# untitled.net
KiCad netlist of a schematic drawn in EAGLE
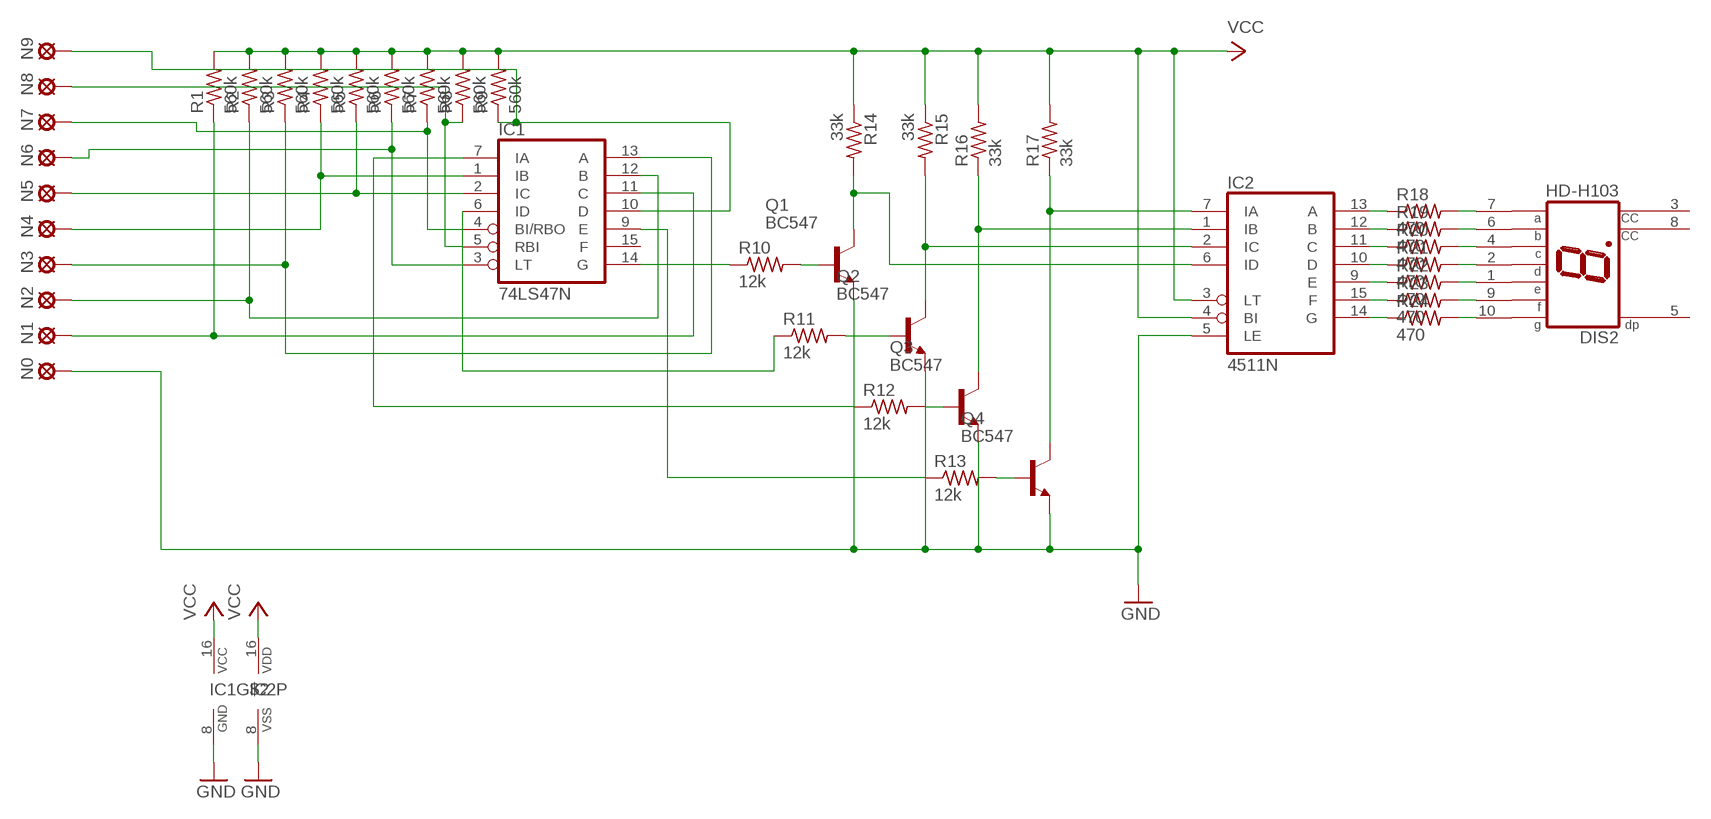
[diagram p0: schematic, sheet 1]

(export (version "E")
  (design (tool "Eeschema 10.0.6"))
  (components
    (comp (ref "DIS2")
      (value "HD-H103")
      (footprint "eagle-import:HDSP-M")
      (libsource (lib "eagle-import") (part "HD-H103"))
    )
    (comp (ref "IC1")
      (value "74LS47N")
      (footprint "eagle-import:DIL16")
      (libsource (lib "eagle-import") (part "7447NLS"))
    )
    (comp (ref "IC2")
      (value "4511N")
      (footprint "eagle-import:DIL16")
      (libsource (lib "eagle-import") (part "4511N"))
    )
    (comp (ref "N0")
      (value "LSP10")
      (footprint "eagle-import:LSP10")
      (libsource (lib "eagle-import") (part "LSP10"))
    )
    (comp (ref "N1")
      (value "LSP10")
      (footprint "eagle-import:LSP10")
      (libsource (lib "eagle-import") (part "LSP10"))
    )
    (comp (ref "N2")
      (value "LSP10")
      (footprint "eagle-import:LSP10")
      (libsource (lib "eagle-import") (part "LSP10"))
    )
    (comp (ref "N3")
      (value "LSP10")
      (footprint "eagle-import:LSP10")
      (libsource (lib "eagle-import") (part "LSP10"))
    )
    (comp (ref "N4")
      (value "LSP10")
      (footprint "eagle-import:LSP10")
      (libsource (lib "eagle-import") (part "LSP10"))
    )
    (comp (ref "N5")
      (value "LSP10")
      (footprint "eagle-import:LSP10")
      (libsource (lib "eagle-import") (part "LSP10"))
    )
    (comp (ref "N6")
      (value "LSP10")
      (footprint "eagle-import:LSP10")
      (libsource (lib "eagle-import") (part "LSP10"))
    )
    (comp (ref "N7")
      (value "LSP10")
      (footprint "eagle-import:LSP10")
      (libsource (lib "eagle-import") (part "LSP10"))
    )
    (comp (ref "N8")
      (value "LSP10")
      (footprint "eagle-import:LSP10")
      (libsource (lib "eagle-import") (part "LSP10"))
    )
    (comp (ref "N9")
      (value "LSP10")
      (footprint "eagle-import:LSP10")
      (libsource (lib "eagle-import") (part "LSP10"))
    )
    (comp (ref "Q1")
      (value "BC547")
      (footprint "eagle-import:TO92")
      (libsource (lib "eagle-import") (part "BC547"))
    )
    (comp (ref "Q2")
      (value "BC547")
      (footprint "eagle-import:TO92")
      (libsource (lib "eagle-import") (part "BC547"))
    )
    (comp (ref "Q3")
      (value "BC547")
      (footprint "eagle-import:TO92")
      (libsource (lib "eagle-import") (part "BC547"))
    )
    (comp (ref "Q4")
      (value "BC547")
      (footprint "eagle-import:TO92")
      (libsource (lib "eagle-import") (part "BC547"))
    )
    (comp (ref "R1")
      (value "560k")
      (footprint "eagle-import:0204_7")
      (libsource (lib "eagle-import") (part "R-US_0204/7"))
    )
    (comp (ref "R2")
      (value "560k")
      (footprint "eagle-import:0204_7")
      (libsource (lib "eagle-import") (part "R-US_0204/7"))
    )
    (comp (ref "R3")
      (value "560k")
      (footprint "eagle-import:0204_7")
      (libsource (lib "eagle-import") (part "R-US_0204/7"))
    )
    (comp (ref "R4")
      (value "560k")
      (footprint "eagle-import:0204_7")
      (libsource (lib "eagle-import") (part "R-US_0204/7"))
    )
    (comp (ref "R5")
      (value "560k")
      (footprint "eagle-import:0204_7")
      (libsource (lib "eagle-import") (part "R-US_0204/7"))
    )
    (comp (ref "R6")
      (value "560k")
      (footprint "eagle-import:0204_7")
      (libsource (lib "eagle-import") (part "R-US_0204/7"))
    )
    (comp (ref "R7")
      (value "560k")
      (footprint "eagle-import:0204_7")
      (libsource (lib "eagle-import") (part "R-US_0204/7"))
    )
    (comp (ref "R8")
      (value "560k")
      (footprint "eagle-import:0204_7")
      (libsource (lib "eagle-import") (part "R-US_0204/7"))
    )
    (comp (ref "R9")
      (value "560k")
      (footprint "eagle-import:0204_7")
      (libsource (lib "eagle-import") (part "R-US_0204/7"))
    )
    (comp (ref "R10")
      (value "12k")
      (footprint "eagle-import:0204_7")
      (libsource (lib "eagle-import") (part "R-US_0204/7"))
    )
    (comp (ref "R11")
      (value "12k")
      (footprint "eagle-import:0204_7")
      (libsource (lib "eagle-import") (part "R-US_0204/7"))
    )
    (comp (ref "R12")
      (value "12k")
      (footprint "eagle-import:0204_7")
      (libsource (lib "eagle-import") (part "R-US_0204/7"))
    )
    (comp (ref "R13")
      (value "12k")
      (footprint "eagle-import:0204_7")
      (libsource (lib "eagle-import") (part "R-US_0204/7"))
    )
    (comp (ref "R14")
      (value "33k")
      (footprint "eagle-import:0204_7")
      (libsource (lib "eagle-import") (part "R-US_0204/7"))
    )
    (comp (ref "R15")
      (value "33k")
      (footprint "eagle-import:0204_7")
      (libsource (lib "eagle-import") (part "R-US_0204/7"))
    )
    (comp (ref "R16")
      (value "33k")
      (footprint "eagle-import:0204_7")
      (libsource (lib "eagle-import") (part "R-US_0204/7"))
    )
    (comp (ref "R17")
      (value "33k")
      (footprint "eagle-import:0204_7")
      (libsource (lib "eagle-import") (part "R-US_0204/7"))
    )
    (comp (ref "R18")
      (value "470")
      (footprint "eagle-import:0204_7")
      (libsource (lib "eagle-import") (part "R-US_0204/7"))
    )
    (comp (ref "R19")
      (value "470")
      (footprint "eagle-import:0204_7")
      (libsource (lib "eagle-import") (part "R-US_0204/7"))
    )
    (comp (ref "R20")
      (value "470")
      (footprint "eagle-import:0204_7")
      (libsource (lib "eagle-import") (part "R-US_0204/7"))
    )
    (comp (ref "R21")
      (value "470")
      (footprint "eagle-import:0204_7")
      (libsource (lib "eagle-import") (part "R-US_0204/7"))
    )
    (comp (ref "R22")
      (value "470")
      (footprint "eagle-import:0204_7")
      (libsource (lib "eagle-import") (part "R-US_0204/7"))
    )
    (comp (ref "R23")
      (value "470")
      (footprint "eagle-import:0204_7")
      (libsource (lib "eagle-import") (part "R-US_0204/7"))
    )
    (comp (ref "R24")
      (value "470")
      (footprint "eagle-import:0204_7")
      (libsource (lib "eagle-import") (part "R-US_0204/7"))
    )
  )
  (nets
    (net (code "1") (name "GND") (class "Default")
      (node (ref "IC1") (pin "8") (pinfunction "GND_8") (pintype "power_in"))
      (node (ref "IC2") (pin "5") (pinfunction "LE_5") (pintype "input"))
      (node (ref "IC2") (pin "8") (pinfunction "VSS_8") (pintype "power_in"))
      (node (ref "N0") (pin "MP") (pinfunction "MP_MP") (pintype "passive"))
      (node (ref "Q1") (pin "1") (pinfunction "E_1") (pintype "passive"))
      (node (ref "Q2") (pin "1") (pinfunction "E_1") (pintype "passive"))
      (node (ref "Q3") (pin "1") (pinfunction "E_1") (pintype "passive"))
      (node (ref "Q4") (pin "1") (pinfunction "E_1") (pintype "passive"))
    )
    (net (code "2") (name "Net-(DIS2-A)") (class "Default")
      (node (ref "DIS2") (pin "7") (pinfunction "A_7") (pintype "passive"))
      (node (ref "R18") (pin "2") (pinfunction "2_2") (pintype "passive"))
    )
    (net (code "3") (name "Net-(DIS2-B)") (class "Default")
      (node (ref "DIS2") (pin "6") (pinfunction "B_6") (pintype "passive"))
      (node (ref "R19") (pin "2") (pinfunction "2_2") (pintype "passive"))
    )
    (net (code "4") (name "Net-(DIS2-C)") (class "Default")
      (node (ref "DIS2") (pin "4") (pinfunction "C_4") (pintype "passive"))
      (node (ref "R20") (pin "2") (pinfunction "2_2") (pintype "passive"))
    )
    (net (code "5") (name "Net-(DIS2-D)") (class "Default")
      (node (ref "DIS2") (pin "2") (pinfunction "D_2") (pintype "passive"))
      (node (ref "R21") (pin "2") (pinfunction "2_2") (pintype "passive"))
    )
    (net (code "6") (name "Net-(DIS2-E)") (class "Default")
      (node (ref "DIS2") (pin "1") (pinfunction "E_1") (pintype "passive"))
      (node (ref "R22") (pin "2") (pinfunction "2_2") (pintype "passive"))
    )
    (net (code "7") (name "Net-(DIS2-F)") (class "Default")
      (node (ref "DIS2") (pin "9") (pinfunction "F_9") (pintype "passive"))
      (node (ref "R23") (pin "2") (pinfunction "2_2") (pintype "passive"))
    )
    (net (code "8") (name "Net-(DIS2-G)") (class "Default")
      (node (ref "DIS2") (pin "10") (pinfunction "G_10") (pintype "passive"))
      (node (ref "R24") (pin "2") (pinfunction "2_2") (pintype "passive"))
    )
    (net (code "9") (name "Net-(IC1A-A)") (class "Default")
      (node (ref "IC1") (pin "13") (pinfunction "A_13") (pintype "output"))
      (node (ref "N3") (pin "MP") (pinfunction "MP_MP") (pintype "passive"))
      (node (ref "R3") (pin "1") (pinfunction "1_1") (pintype "passive"))
    )
    (net (code "10") (name "Net-(IC1A-B)") (class "Default")
      (node (ref "IC1") (pin "12") (pinfunction "B_12") (pintype "output"))
      (node (ref "N2") (pin "MP") (pinfunction "MP_MP") (pintype "passive"))
      (node (ref "R2") (pin "1") (pinfunction "1_1") (pintype "passive"))
    )
    (net (code "11") (name "Net-(IC1A-BI{slash}RBO)") (class "Default")
      (node (ref "IC1") (pin "4") (pinfunction "BI/RBO_4") (pintype "input"))
      (node (ref "N7") (pin "MP") (pinfunction "MP_MP") (pintype "passive"))
      (node (ref "R7") (pin "1") (pinfunction "1_1") (pintype "passive"))
    )
    (net (code "12") (name "Net-(IC1A-C)") (class "Default")
      (node (ref "IC1") (pin "11") (pinfunction "C_11") (pintype "output"))
      (node (ref "N1") (pin "MP") (pinfunction "MP_MP") (pintype "passive"))
      (node (ref "R1") (pin "1") (pinfunction "1_1") (pintype "passive"))
    )
    (net (code "13") (name "Net-(IC1A-D)") (class "Default")
      (node (ref "IC1") (pin "10") (pinfunction "D_10") (pintype "output"))
      (node (ref "N9") (pin "MP") (pinfunction "MP_MP") (pintype "passive"))
      (node (ref "R9") (pin "1") (pinfunction "1_1") (pintype "passive"))
    )
    (net (code "14") (name "Net-(IC1A-E)") (class "Default")
      (node (ref "IC1") (pin "9") (pinfunction "E_9") (pintype "output"))
      (node (ref "R13") (pin "1") (pinfunction "1_1") (pintype "passive"))
    )
    (net (code "15") (name "Net-(IC1A-G)") (class "Default")
      (node (ref "IC1") (pin "14") (pinfunction "G_14") (pintype "output"))
      (node (ref "R10") (pin "1") (pinfunction "1_1") (pintype "passive"))
    )
    (net (code "16") (name "Net-(IC1A-IA)") (class "Default")
      (node (ref "IC1") (pin "7") (pinfunction "IA_7") (pintype "input"))
      (node (ref "R12") (pin "1") (pinfunction "1_1") (pintype "passive"))
    )
    (net (code "17") (name "Net-(IC1A-IB)") (class "Default")
      (node (ref "IC1") (pin "1") (pinfunction "IB_1") (pintype "input"))
      (node (ref "N4") (pin "MP") (pinfunction "MP_MP") (pintype "passive"))
      (node (ref "R4") (pin "1") (pinfunction "1_1") (pintype "passive"))
    )
    (net (code "18") (name "Net-(IC1A-IC)") (class "Default")
      (node (ref "IC1") (pin "2") (pinfunction "IC_2") (pintype "input"))
      (node (ref "N5") (pin "MP") (pinfunction "MP_MP") (pintype "passive"))
      (node (ref "R5") (pin "1") (pinfunction "1_1") (pintype "passive"))
    )
    (net (code "19") (name "Net-(IC1A-ID)") (class "Default")
      (node (ref "IC1") (pin "6") (pinfunction "ID_6") (pintype "input"))
      (node (ref "R11") (pin "1") (pinfunction "1_1") (pintype "passive"))
    )
    (net (code "20") (name "Net-(IC1A-LT)") (class "Default")
      (node (ref "IC1") (pin "3") (pinfunction "LT_3") (pintype "input"))
      (node (ref "N6") (pin "MP") (pinfunction "MP_MP") (pintype "passive"))
      (node (ref "R6") (pin "1") (pinfunction "1_1") (pintype "passive"))
    )
    (net (code "21") (name "Net-(IC1A-RBI)") (class "Default")
      (node (ref "IC1") (pin "5") (pinfunction "RBI_5") (pintype "input"))
      (node (ref "N8") (pin "MP") (pinfunction "MP_MP") (pintype "passive"))
      (node (ref "R8") (pin "1") (pinfunction "1_1") (pintype "passive"))
    )
    (net (code "22") (name "Net-(IC2A-A)") (class "Default")
      (node (ref "IC2") (pin "13") (pinfunction "A_13") (pintype "output"))
      (node (ref "R18") (pin "1") (pinfunction "1_1") (pintype "passive"))
    )
    (net (code "23") (name "Net-(IC2A-B)") (class "Default")
      (node (ref "IC2") (pin "12") (pinfunction "B_12") (pintype "output"))
      (node (ref "R19") (pin "1") (pinfunction "1_1") (pintype "passive"))
    )
    (net (code "24") (name "Net-(IC2A-C)") (class "Default")
      (node (ref "IC2") (pin "11") (pinfunction "C_11") (pintype "output"))
      (node (ref "R20") (pin "1") (pinfunction "1_1") (pintype "passive"))
    )
    (net (code "25") (name "Net-(IC2A-D)") (class "Default")
      (node (ref "IC2") (pin "10") (pinfunction "D_10") (pintype "output"))
      (node (ref "R21") (pin "1") (pinfunction "1_1") (pintype "passive"))
    )
    (net (code "26") (name "Net-(IC2A-E)") (class "Default")
      (node (ref "IC2") (pin "9") (pinfunction "E_9") (pintype "output"))
      (node (ref "R22") (pin "1") (pinfunction "1_1") (pintype "passive"))
    )
    (net (code "27") (name "Net-(IC2A-F)") (class "Default")
      (node (ref "IC2") (pin "15") (pinfunction "F_15") (pintype "output"))
      (node (ref "R23") (pin "1") (pinfunction "1_1") (pintype "passive"))
    )
    (net (code "28") (name "Net-(IC2A-G)") (class "Default")
      (node (ref "IC2") (pin "14") (pinfunction "G_14") (pintype "output"))
      (node (ref "R24") (pin "1") (pinfunction "1_1") (pintype "passive"))
    )
    (net (code "29") (name "Net-(IC2A-IA)") (class "Default")
      (node (ref "IC2") (pin "7") (pinfunction "IA_7") (pintype "input"))
      (node (ref "Q4") (pin "3") (pinfunction "C_3") (pintype "passive"))
      (node (ref "R17") (pin "1") (pinfunction "1_1") (pintype "passive"))
    )
    (net (code "30") (name "Net-(IC2A-IB)") (class "Default")
      (node (ref "IC2") (pin "1") (pinfunction "IB_1") (pintype "input"))
      (node (ref "Q3") (pin "3") (pinfunction "C_3") (pintype "passive"))
      (node (ref "R16") (pin "1") (pinfunction "1_1") (pintype "passive"))
    )
    (net (code "31") (name "Net-(IC2A-IC)") (class "Default")
      (node (ref "IC2") (pin "2") (pinfunction "IC_2") (pintype "input"))
      (node (ref "Q2") (pin "3") (pinfunction "C_3") (pintype "passive"))
      (node (ref "R15") (pin "2") (pinfunction "2_2") (pintype "passive"))
    )
    (net (code "32") (name "Net-(IC2A-ID)") (class "Default")
      (node (ref "IC2") (pin "6") (pinfunction "ID_6") (pintype "input"))
      (node (ref "Q1") (pin "3") (pinfunction "C_3") (pintype "passive"))
      (node (ref "R14") (pin "2") (pinfunction "2_2") (pintype "passive"))
    )
    (net (code "33") (name "Net-(Q1-B)") (class "Default")
      (node (ref "Q1") (pin "2") (pinfunction "B_2") (pintype "passive"))
      (node (ref "R10") (pin "2") (pinfunction "2_2") (pintype "passive"))
    )
    (net (code "34") (name "Net-(Q2-B)") (class "Default")
      (node (ref "Q2") (pin "2") (pinfunction "B_2") (pintype "passive"))
      (node (ref "R11") (pin "2") (pinfunction "2_2") (pintype "passive"))
    )
    (net (code "35") (name "Net-(Q3-B)") (class "Default")
      (node (ref "Q3") (pin "2") (pinfunction "B_2") (pintype "passive"))
      (node (ref "R12") (pin "2") (pinfunction "2_2") (pintype "passive"))
    )
    (net (code "36") (name "Net-(Q4-B)") (class "Default")
      (node (ref "Q4") (pin "2") (pinfunction "B_2") (pintype "passive"))
      (node (ref "R13") (pin "2") (pinfunction "2_2") (pintype "passive"))
    )
    (net (code "37") (name "VCC") (class "Default")
      (node (ref "IC1") (pin "16") (pinfunction "VCC_16") (pintype "power_in"))
      (node (ref "IC2") (pin "16") (pinfunction "VDD_16") (pintype "power_in"))
      (node (ref "IC2") (pin "3") (pinfunction "LT_3") (pintype "input"))
      (node (ref "IC2") (pin "4") (pinfunction "BI_4") (pintype "input"))
      (node (ref "R1") (pin "2") (pinfunction "2_2") (pintype "passive"))
      (node (ref "R14") (pin "1") (pinfunction "1_1") (pintype "passive"))
      (node (ref "R15") (pin "1") (pinfunction "1_1") (pintype "passive"))
      (node (ref "R16") (pin "2") (pinfunction "2_2") (pintype "passive"))
      (node (ref "R17") (pin "2") (pinfunction "2_2") (pintype "passive"))
      (node (ref "R2") (pin "2") (pinfunction "2_2") (pintype "passive"))
      (node (ref "R3") (pin "2") (pinfunction "2_2") (pintype "passive"))
      (node (ref "R4") (pin "2") (pinfunction "2_2") (pintype "passive"))
      (node (ref "R5") (pin "2") (pinfunction "2_2") (pintype "passive"))
      (node (ref "R6") (pin "2") (pinfunction "2_2") (pintype "passive"))
      (node (ref "R7") (pin "2") (pinfunction "2_2") (pintype "passive"))
      (node (ref "R8") (pin "2") (pinfunction "2_2") (pintype "passive"))
      (node (ref "R9") (pin "2") (pinfunction "2_2") (pintype "passive"))
    )
    (net (code "38") (name "unconnected-(DIS2-CC-Pad3)") (class "Default")
      (node (ref "DIS2") (pin "3") (pinfunction "CC_3") (pintype "passive"))
    )
    (net (code "39") (name "unconnected-(DIS2-CC-Pad8)") (class "Default")
      (node (ref "DIS2") (pin "8") (pinfunction "CC_8") (pintype "passive"))
    )
    (net (code "40") (name "unconnected-(DIS2-DP-Pad5)") (class "Default")
      (node (ref "DIS2") (pin "5") (pinfunction "DP_5") (pintype "passive"))
    )
    (net (code "41") (name "unconnected-(IC1A-F-Pad15)") (class "Default")
      (node (ref "IC1") (pin "15") (pinfunction "F_15") (pintype "output"))
    )
  )
)
